# gameboypocket.net
KiCad netlist of a schematic drawn in EAGLE
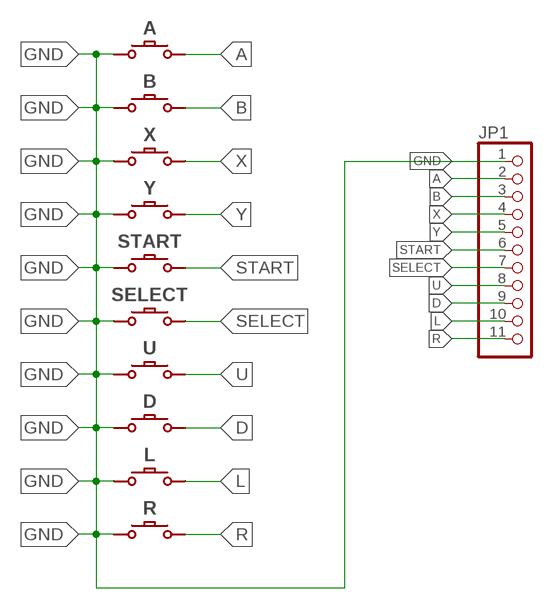
[diagram p0: schematic, sheet 1]

(export (version "E")
  (design (tool "Eeschema 10.0.6"))
  (components
    (comp (ref "A")
      (value "CONDUCTIVE_BUTTON")
      (footprint "eagle-import:CONDUCTIVE_BUTTON")
      (libsource (lib "eagle-import") (part "CONDUCTIVE_BUTTON"))
    )
    (comp (ref "B")
      (value "CONDUCTIVE_BUTTON")
      (footprint "eagle-import:CONDUCTIVE_BUTTON")
      (libsource (lib "eagle-import") (part "CONDUCTIVE_BUTTON"))
    )
    (comp (ref "D")
      (value "CONDUCTIVE_BUTTON")
      (footprint "eagle-import:CONDUCTIVE_BUTTON")
      (libsource (lib "eagle-import") (part "CONDUCTIVE_BUTTON"))
    )
    (comp (ref "JP1")
      (value "PINHD-1X11")
      (footprint "eagle-import:1X11")
      (libsource (lib "eagle-import") (part "PINHD-1X11"))
    )
    (comp (ref "L")
      (value "CONDUCTIVE_BUTTON")
      (footprint "eagle-import:CONDUCTIVE_BUTTON")
      (libsource (lib "eagle-import") (part "CONDUCTIVE_BUTTON"))
    )
    (comp (ref "R")
      (value "CONDUCTIVE_BUTTON")
      (footprint "eagle-import:CONDUCTIVE_BUTTON")
      (libsource (lib "eagle-import") (part "CONDUCTIVE_BUTTON"))
    )
    (comp (ref "SELECT")
      (value "CONDUCTIVE_BUTTON_STARTSELECT")
      (footprint "eagle-import:CONDUCTIVE_BUTTON_STARTSELECT")
      (libsource (lib "eagle-import") (part "CONDUCTIVE_BUTTON_STARTSELECT"))
    )
    (comp (ref "START")
      (value "CONDUCTIVE_BUTTON_STARTSELECT")
      (footprint "eagle-import:CONDUCTIVE_BUTTON_STARTSELECT")
      (libsource (lib "eagle-import") (part "CONDUCTIVE_BUTTON_STARTSELECT"))
    )
    (comp (ref "U")
      (value "CONDUCTIVE_BUTTON")
      (footprint "eagle-import:CONDUCTIVE_BUTTON")
      (libsource (lib "eagle-import") (part "CONDUCTIVE_BUTTON"))
    )
    (comp (ref "X")
      (value "CONDUCTIVE_BUTTON_DRILL")
      (footprint "eagle-import:CONDUCTIVE_BUTTON_DRILL")
      (libsource (lib "eagle-import") (part "CONDUCTIVE_BUTTON_DRILL"))
    )
    (comp (ref "Y")
      (value "CONDUCTIVE_BUTTON_DRILL")
      (footprint "eagle-import:CONDUCTIVE_BUTTON_DRILL")
      (libsource (lib "eagle-import") (part "CONDUCTIVE_BUTTON_DRILL"))
    )
  )
  (nets
    (net (code "1") (name "A") (class "Default")
      (node (ref "A") (pin "P$ACTIVE") (pinfunction "P$ACTIVE_P$ACTIVE") (pintype "bidirectional"))
      (node (ref "JP1") (pin "2") (pinfunction "2_2") (pintype "passive"))
    )
    (net (code "2") (name "B") (class "Default")
      (node (ref "B") (pin "P$ACTIVE") (pinfunction "P$ACTIVE_P$ACTIVE") (pintype "bidirectional"))
      (node (ref "JP1") (pin "3") (pinfunction "3_3") (pintype "passive"))
    )
    (net (code "3") (name "D") (class "Default")
      (node (ref "D") (pin "P$ACTIVE") (pinfunction "P$ACTIVE_P$ACTIVE") (pintype "bidirectional"))
      (node (ref "JP1") (pin "9") (pinfunction "9_9") (pintype "passive"))
    )
    (net (code "4") (name "GND") (class "Default")
      (node (ref "A") (pin "P$GND") (pinfunction "P$GND_P$GND") (pintype "bidirectional"))
      (node (ref "B") (pin "P$GND") (pinfunction "P$GND_P$GND") (pintype "bidirectional"))
      (node (ref "D") (pin "P$GND") (pinfunction "P$GND_P$GND") (pintype "bidirectional"))
      (node (ref "JP1") (pin "1") (pinfunction "1_1") (pintype "passive"))
      (node (ref "L") (pin "P$GND") (pinfunction "P$GND_P$GND") (pintype "bidirectional"))
      (node (ref "R") (pin "P$GND") (pinfunction "P$GND_P$GND") (pintype "bidirectional"))
      (node (ref "SELECT") (pin "P$GND") (pinfunction "P$GND_P$GND") (pintype "bidirectional"))
      (node (ref "START") (pin "P$GND") (pinfunction "P$GND_P$GND") (pintype "bidirectional"))
      (node (ref "U") (pin "P$GND") (pinfunction "P$GND_P$GND") (pintype "bidirectional"))
      (node (ref "X") (pin "P$GND") (pinfunction "P$GND_P$GND") (pintype "bidirectional"))
      (node (ref "Y") (pin "P$GND") (pinfunction "P$GND_P$GND") (pintype "bidirectional"))
    )
    (net (code "5") (name "L") (class "Default")
      (node (ref "JP1") (pin "10") (pinfunction "10_10") (pintype "passive"))
      (node (ref "L") (pin "P$ACTIVE") (pinfunction "P$ACTIVE_P$ACTIVE") (pintype "bidirectional"))
    )
    (net (code "6") (name "R") (class "Default")
      (node (ref "JP1") (pin "11") (pinfunction "11_11") (pintype "passive"))
      (node (ref "R") (pin "P$ACTIVE") (pinfunction "P$ACTIVE_P$ACTIVE") (pintype "bidirectional"))
    )
    (net (code "7") (name "SELECT") (class "Default")
      (node (ref "JP1") (pin "7") (pinfunction "7_7") (pintype "passive"))
      (node (ref "SELECT") (pin "P$ACTIVE") (pinfunction "P$ACTIVE_P$ACTIVE") (pintype "bidirectional"))
    )
    (net (code "8") (name "START") (class "Default")
      (node (ref "JP1") (pin "6") (pinfunction "6_6") (pintype "passive"))
      (node (ref "START") (pin "P$ACTIVE") (pinfunction "P$ACTIVE_P$ACTIVE") (pintype "bidirectional"))
    )
    (net (code "9") (name "U") (class "Default")
      (node (ref "JP1") (pin "8") (pinfunction "8_8") (pintype "passive"))
      (node (ref "U") (pin "P$ACTIVE") (pinfunction "P$ACTIVE_P$ACTIVE") (pintype "bidirectional"))
    )
    (net (code "10") (name "X") (class "Default")
      (node (ref "JP1") (pin "4") (pinfunction "4_4") (pintype "passive"))
      (node (ref "X") (pin "P$ACTIVE") (pinfunction "P$ACTIVE_P$ACTIVE") (pintype "bidirectional"))
    )
    (net (code "11") (name "Y") (class "Default")
      (node (ref "JP1") (pin "5") (pinfunction "5_5") (pintype "passive"))
      (node (ref "Y") (pin "P$ACTIVE") (pinfunction "P$ACTIVE_P$ACTIVE") (pintype "bidirectional"))
    )
  )
)
